# Currnet_Shunt.net
KiCad netlist of a schematic drawn in EAGLE
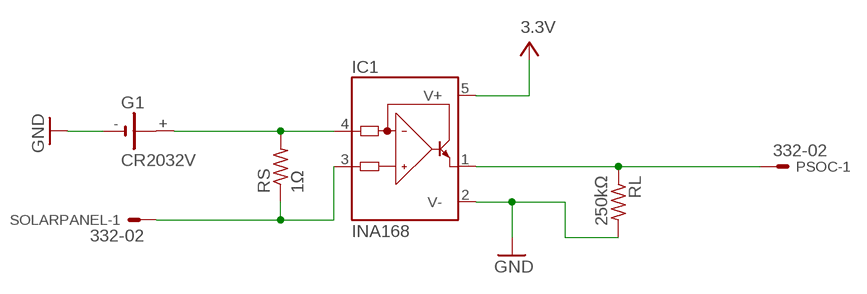
[diagram p0: schematic, sheet 1]

(export (version "E")
  (design (tool "Eeschema 10.0.6"))
  (components
    (comp (ref "G1")
      (value "CR2032V")
      (footprint "eagle-import:CR2032V")
      (libsource (lib "eagle-import") (part "CR2032V"))
    )
    (comp (ref "IC1")
      (value "INA168")
      (footprint "eagle-import:SOT23-5")
      (fields (field (name "MF") "TEXAS INSTRUMENTS") (field (name "MPN") "INA168NA/250"))
      (libsource (lib "eagle-import") (part "INA168"))
    )
    (comp (ref "PSOC")
      (value "332-02")
      (footprint "eagle-import:332-02")
      (libsource (lib "eagle-import") (part "332-02"))
    )
    (comp (ref "RL")
      (value "250kΩ")
      (footprint "eagle-import:0204V")
      (libsource (lib "eagle-import") (part "R-US_0204/2V"))
    )
    (comp (ref "RS")
      (value "1Ω")
      (footprint "eagle-import:0204V")
      (libsource (lib "eagle-import") (part "R-US_0204/2V"))
    )
    (comp (ref "SOLARPANEL")
      (value "332-02")
      (footprint "eagle-import:332-02")
      (libsource (lib "eagle-import") (part "332-02"))
    )
  )
  (nets
    (net (code "1") (name "3.3V") (class "Default")
      (node (ref "IC1") (pin "5") (pinfunction "V+_5") (pintype "power_in"))
    )
    (net (code "2") (name "GND") (class "Default")
      (node (ref "G1") (pin "-") (pinfunction "-_-") (pintype "passive"))
      (node (ref "IC1") (pin "2") (pinfunction "V-_2") (pintype "power_in"))
      (node (ref "RL") (pin "2") (pinfunction "2_2") (pintype "passive"))
    )
    (net (code "3") (name "Net-(IC1-IN+)") (class "Default")
      (node (ref "IC1") (pin "3") (pinfunction "IN+_3") (pintype "input"))
      (node (ref "RS") (pin "1") (pinfunction "1_1") (pintype "passive"))
      (node (ref "SOLARPANEL") (pin "1") (pinfunction "S_1") (pintype "passive"))
    )
    (net (code "4") (name "Net-(IC1-IN-)") (class "Default")
      (node (ref "G1") (pin "+") (pinfunction "+_+") (pintype "passive"))
      (node (ref "IC1") (pin "4") (pinfunction "IN-_4") (pintype "input"))
      (node (ref "RS") (pin "2") (pinfunction "2_2") (pintype "passive"))
    )
    (net (code "5") (name "Net-(IC1-OUT)") (class "Default")
      (node (ref "IC1") (pin "1") (pinfunction "OUT_1") (pintype "output"))
      (node (ref "PSOC") (pin "1") (pinfunction "S_1") (pintype "passive"))
      (node (ref "RL") (pin "1") (pinfunction "1_1") (pintype "passive"))
    )
    (net (code "6") (name "unconnected-(G1-+-Pad+@1)") (class "Default")
      (node (ref "G1") (pin "+@1") (pinfunction "+_+@1") (pintype "passive"))
    )
  )
)
